# PWR.net
KiCad netlist of a schematic drawn in EAGLE
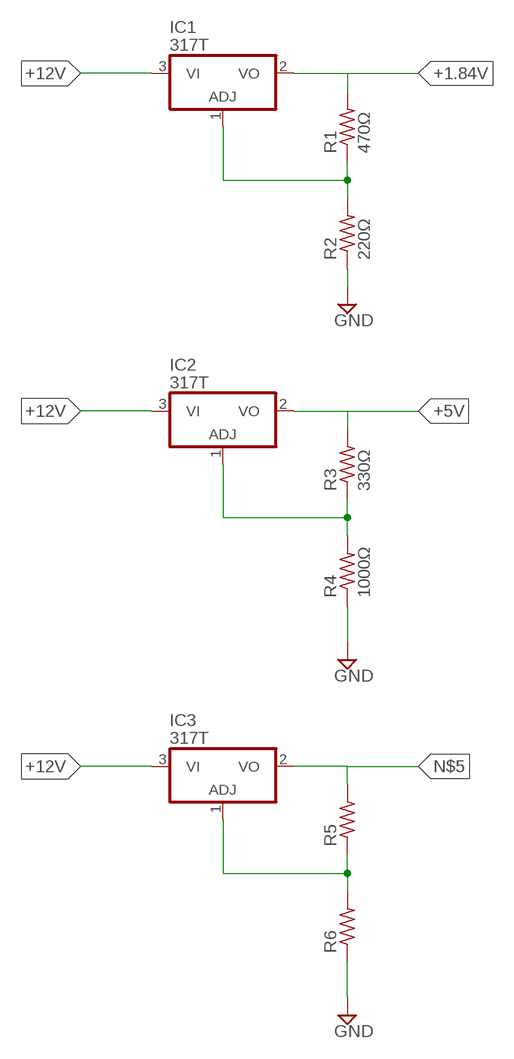
[diagram p0: schematic, sheet 1]

(export (version "E")
  (design (tool "Eeschema 10.0.6"))
  (components
    (comp (ref "IC1")
      (value "317T")
      (footprint "eagle-import:TO220H")
      (libsource (lib "eagle-import") (part "317T"))
    )
    (comp (ref "IC2")
      (value "317T")
      (footprint "eagle-import:TO220H")
      (libsource (lib "eagle-import") (part "317T"))
    )
    (comp (ref "IC3")
      (value "317T")
      (footprint "eagle-import:TO220H")
      (libsource (lib "eagle-import") (part "317T"))
    )
    (comp (ref "R1")
      (value "470Ω")
      (footprint "eagle-import:0204_7")
      (libsource (lib "eagle-import") (part "R-US_0204/7"))
    )
    (comp (ref "R2")
      (value "220Ω")
      (footprint "eagle-import:0204_7")
      (libsource (lib "eagle-import") (part "R-US_0204/7"))
    )
    (comp (ref "R3")
      (value "330Ω")
      (footprint "eagle-import:0204_7")
      (libsource (lib "eagle-import") (part "R-US_0204/7"))
    )
    (comp (ref "R4")
      (value "1000Ω")
      (footprint "eagle-import:0204_7")
      (libsource (lib "eagle-import") (part "R-US_0204/7"))
    )
    (comp (ref "R5")
      (value "R-US_0204/7")
      (footprint "eagle-import:0204_7")
      (libsource (lib "eagle-import") (part "R-US_0204/7"))
    )
    (comp (ref "R6")
      (value "R-US_0204/7")
      (footprint "eagle-import:0204_7")
      (libsource (lib "eagle-import") (part "R-US_0204/7"))
    )
  )
  (nets
    (net (code "1") (name "+1.84V") (class "Default")
      (node (ref "IC1") (pin "2") (pinfunction "VO_2") (pintype "passive"))
      (node (ref "R1") (pin "2") (pinfunction "2_2") (pintype "passive"))
    )
    (net (code "2") (name "+5V") (class "Default")
      (node (ref "IC2") (pin "2") (pinfunction "VO_2") (pintype "passive"))
      (node (ref "R3") (pin "2") (pinfunction "2_2") (pintype "passive"))
    )
    (net (code "3") (name "+12V") (class "Default")
      (node (ref "IC1") (pin "3") (pinfunction "VI_3") (pintype "input"))
      (node (ref "IC2") (pin "3") (pinfunction "VI_3") (pintype "input"))
      (node (ref "IC3") (pin "3") (pinfunction "VI_3") (pintype "input"))
    )
    (net (code "4") (name "GND") (class "Default")
      (node (ref "R2") (pin "1") (pinfunction "1_1") (pintype "passive"))
      (node (ref "R4") (pin "1") (pinfunction "1_1") (pintype "passive"))
      (node (ref "R6") (pin "1") (pinfunction "1_1") (pintype "passive"))
    )
    (net (code "5") (name "N$5") (class "Default")
      (node (ref "IC3") (pin "2") (pinfunction "VO_2") (pintype "passive"))
      (node (ref "R5") (pin "2") (pinfunction "2_2") (pintype "passive"))
    )
    (net (code "6") (name "Net-(IC1-ADJ)") (class "Default")
      (node (ref "IC1") (pin "1") (pinfunction "ADJ_1") (pintype "input"))
      (node (ref "R1") (pin "1") (pinfunction "1_1") (pintype "passive"))
      (node (ref "R2") (pin "2") (pinfunction "2_2") (pintype "passive"))
    )
    (net (code "7") (name "Net-(IC2-ADJ)") (class "Default")
      (node (ref "IC2") (pin "1") (pinfunction "ADJ_1") (pintype "input"))
      (node (ref "R3") (pin "1") (pinfunction "1_1") (pintype "passive"))
      (node (ref "R4") (pin "2") (pinfunction "2_2") (pintype "passive"))
    )
    (net (code "8") (name "Net-(IC3-ADJ)") (class "Default")
      (node (ref "IC3") (pin "1") (pinfunction "ADJ_1") (pintype "input"))
      (node (ref "R5") (pin "1") (pinfunction "1_1") (pintype "passive"))
      (node (ref "R6") (pin "2") (pinfunction "2_2") (pintype "passive"))
    )
  )
)
